# Sheet2.net
KiCad netlist of a schematic drawn in Altium Designer
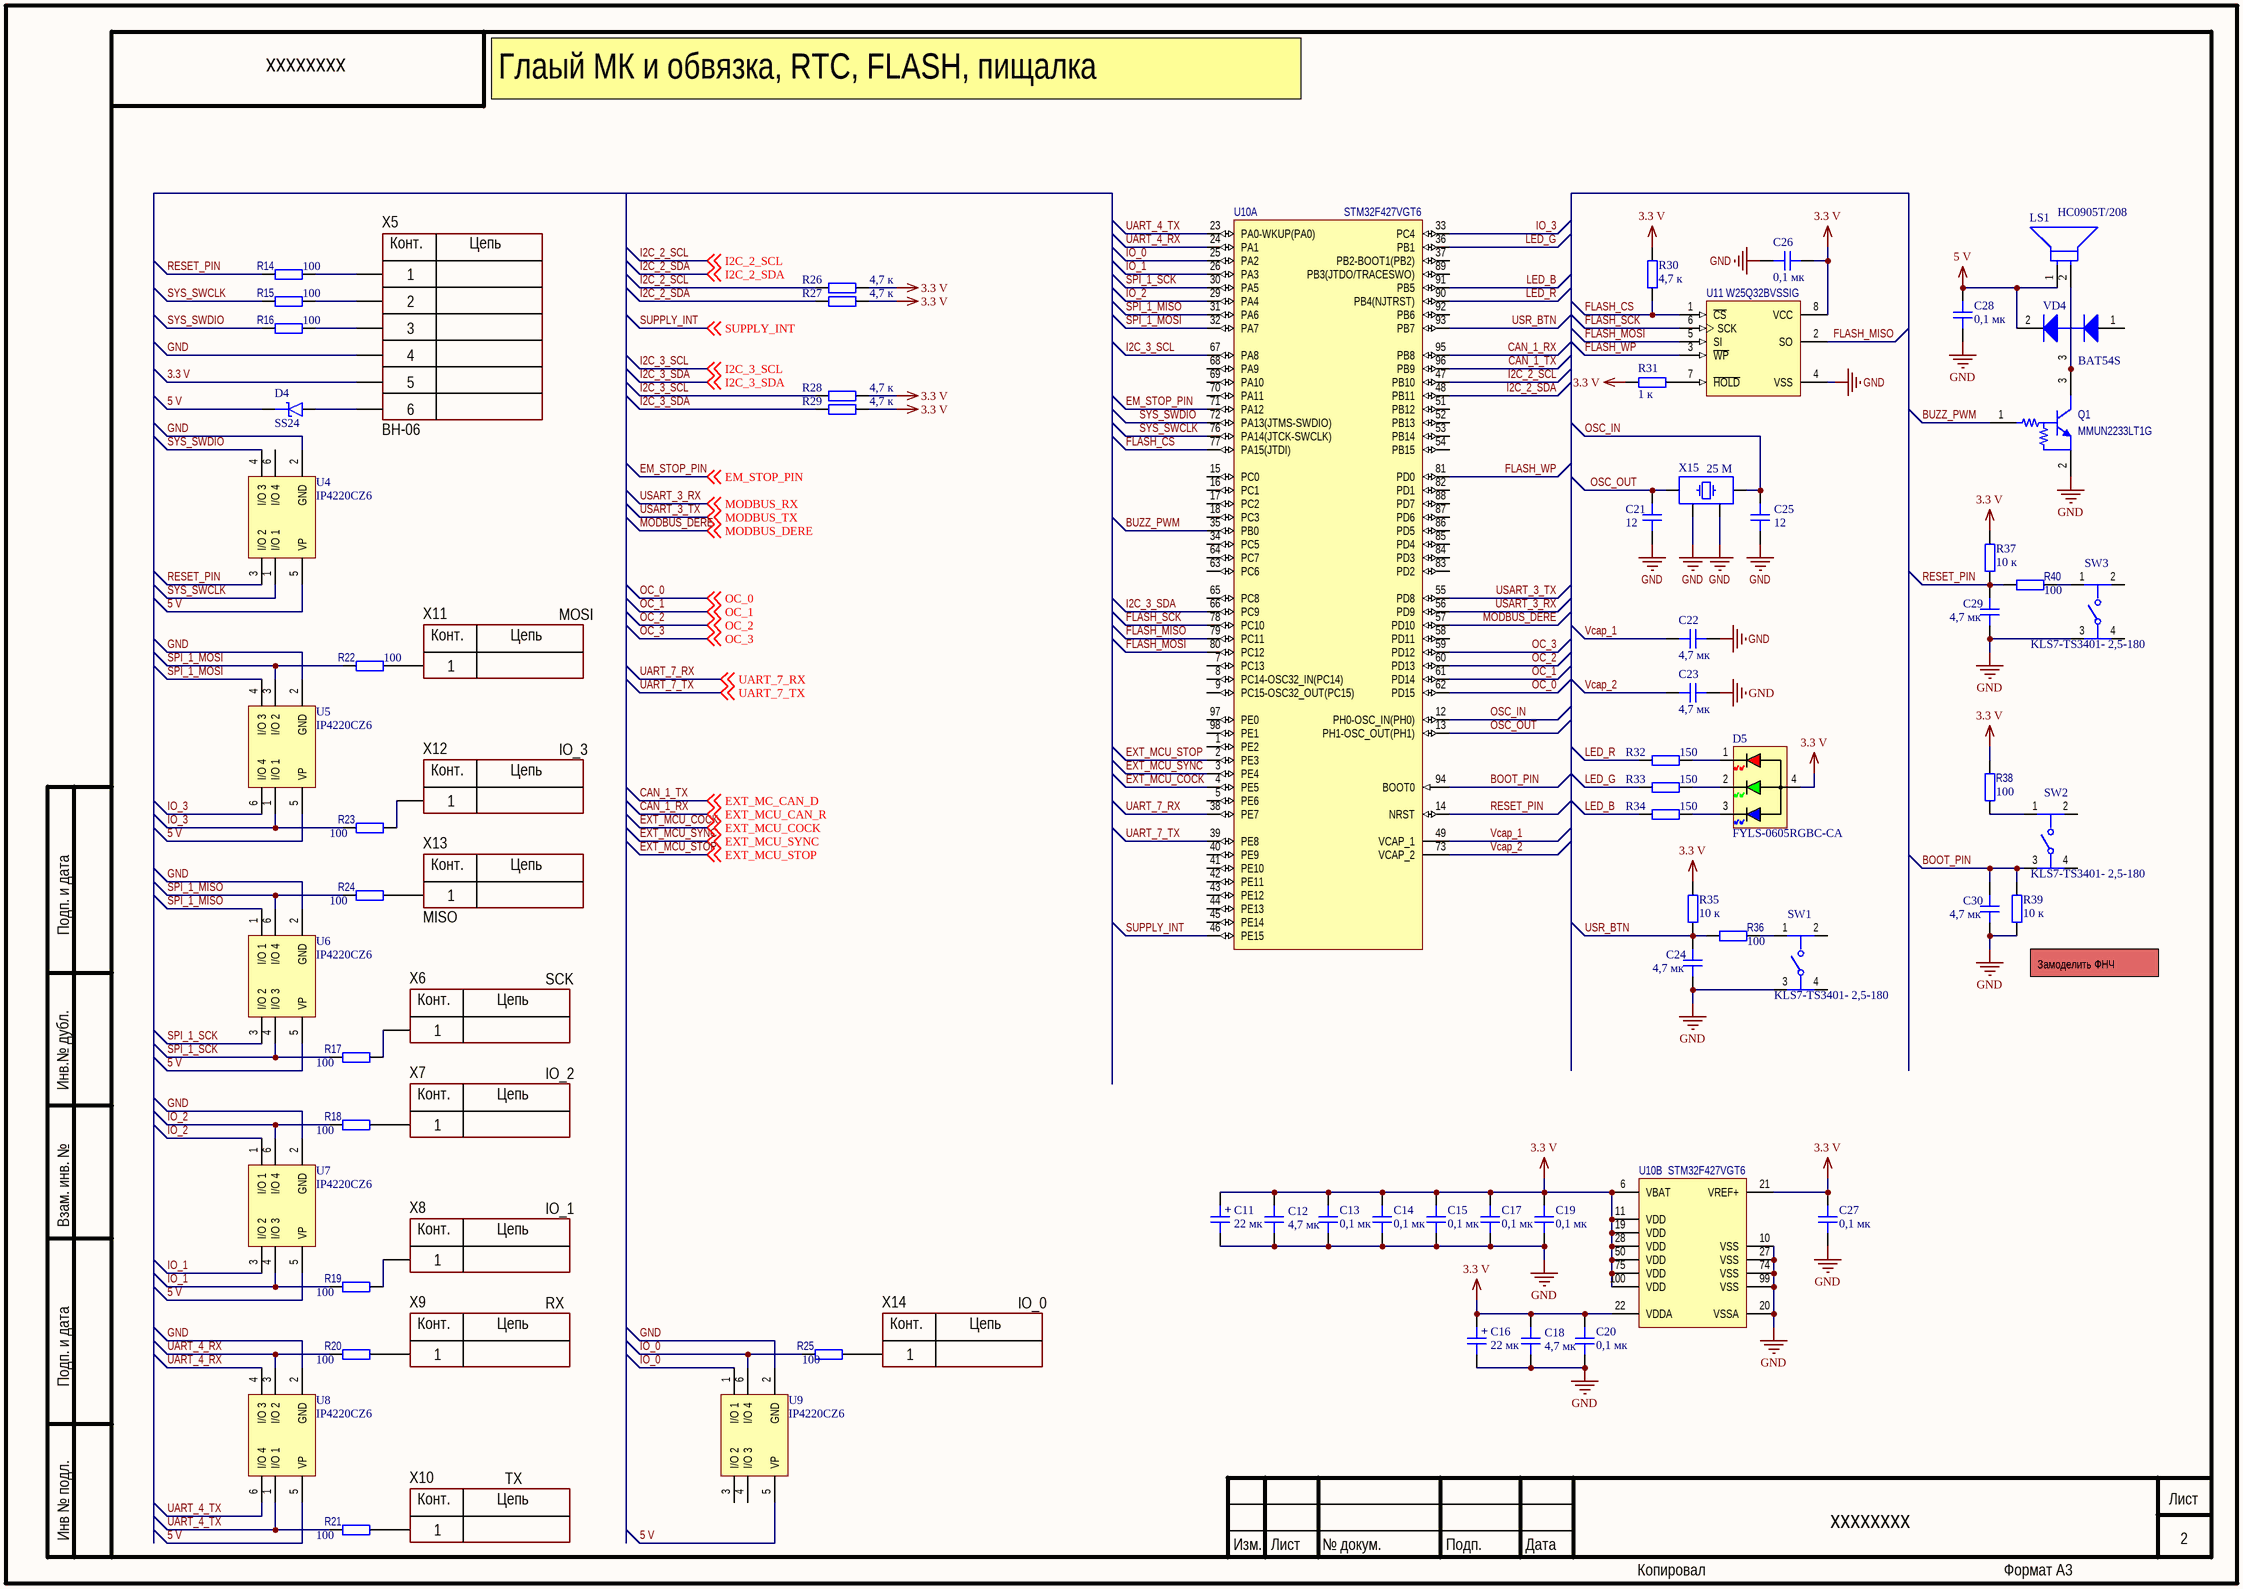
[diagram p0: Sheet2.SchDoc]

(export (version "E")
  (design (tool "Eeschema 10.0.6"))
  (components
    (comp (ref "C11")
      (value "22 мк")
      (footprint "TANTAL_B")
      (description "Танталовый конденсатор")
      (fields (field (name "VOLTAGE") "6,3"))
      (libsource (lib "Schematic-Lib-PhilsLab") (part "CAP_ALEL_16x16.5_25V"))
    )
    (comp (ref "C12")
      (value "4,7 мк")
      (footprint "CAP_0805")
      (description "Керамический конденсатор")
      (libsource (lib "Schematic-Lib-PhilsLab") (part "CAP_0805"))
    )
    (comp (ref "C13")
      (value "0,1 мк")
      (footprint "CAP_0603")
      (description "Керамический конденсатор")
      (libsource (lib "Schematic-Lib-PhilsLab") (part "CAP_0603"))
    )
    (comp (ref "C14")
      (value "0,1 мк")
      (footprint "CAP_0603")
      (description "Керамический конденсатор")
      (libsource (lib "Schematic-Lib-PhilsLab") (part "CAP_0603"))
    )
    (comp (ref "C15")
      (value "0,1 мк")
      (footprint "CAP_0603")
      (description "Керамический конденсатор")
      (libsource (lib "Schematic-Lib-PhilsLab") (part "CAP_0603"))
    )
    (comp (ref "C16")
      (value "22 мк")
      (footprint "TANTAL_B")
      (description "Танталовый конденсатор")
      (fields (field (name "VOLTAGE") "6,3"))
      (libsource (lib "Schematic-Lib-PhilsLab") (part "CAP_ALEL_16x16.5_25V"))
    )
    (comp (ref "C17")
      (value "0,1 мк")
      (footprint "CAP_0603")
      (description "Керамический конденсатор")
      (libsource (lib "Schematic-Lib-PhilsLab") (part "CAP_0603"))
    )
    (comp (ref "C18")
      (value "4,7 мк")
      (footprint "CAP_0805")
      (description "Керамический конденсатор")
      (libsource (lib "Schematic-Lib-PhilsLab") (part "CAP_0805"))
    )
    (comp (ref "C19")
      (value "0,1 мк")
      (footprint "CAP_0603")
      (description "Керамический конденсатор")
      (libsource (lib "Schematic-Lib-PhilsLab") (part "CAP_0603"))
    )
    (comp (ref "C20")
      (value "0,1 мк")
      (footprint "CAP_0603")
      (description "Керамический конденсатор")
      (libsource (lib "Schematic-Lib-PhilsLab") (part "CAP_0603"))
    )
    (comp (ref "C21")
      (value "12")
      (footprint "CAP_0603")
      (description "Керамический конденсатор")
      (libsource (lib "Schematic-Lib-PhilsLab") (part "CAP_0603"))
    )
    (comp (ref "C22")
      (value "4,7 мк")
      (footprint "CAP_0805")
      (description "Керамический конденсатор")
      (libsource (lib "Schematic-Lib-PhilsLab") (part "CAP_0805"))
    )
    (comp (ref "C23")
      (value "4,7 мк")
      (footprint "CAP_0805")
      (description "Керамический конденсатор")
      (libsource (lib "Schematic-Lib-PhilsLab") (part "CAP_0805"))
    )
    (comp (ref "C24")
      (value "4,7 мк")
      (footprint "CAP_0805")
      (description "Керамический конденсатор")
      (libsource (lib "Schematic-Lib-PhilsLab") (part "CAP_0805"))
    )
    (comp (ref "C25")
      (value "12")
      (footprint "CAP_0603")
      (description "Керамический конденсатор")
      (libsource (lib "Schematic-Lib-PhilsLab") (part "CAP_0603"))
    )
    (comp (ref "C26")
      (value "0,1 мк")
      (footprint "CAP_0603")
      (description "Керамический конденсатор")
      (libsource (lib "Schematic-Lib-PhilsLab") (part "CAP_0603"))
    )
    (comp (ref "C27")
      (value "0,1 мк")
      (footprint "CAP_0603")
      (description "Керамический конденсатор")
      (libsource (lib "Schematic-Lib-PhilsLab") (part "CAP_0603"))
    )
    (comp (ref "C28")
      (value "0,1 мк")
      (footprint "CAP_0603")
      (description "Керамический конденсатор")
      (libsource (lib "Schematic-Lib-PhilsLab") (part "CAP_0603"))
    )
    (comp (ref "C29")
      (value "4,7 мк")
      (footprint "CAP_0805")
      (description "Керамический конденсатор")
      (libsource (lib "Schematic-Lib-PhilsLab") (part "CAP_0805"))
    )
    (comp (ref "C30")
      (value "4,7 мк")
      (footprint "CAP_0805")
      (description "Керамический конденсатор")
      (libsource (lib "Schematic-Lib-PhilsLab") (part "CAP_0805"))
    )
    (comp (ref "D4")
      (value "SS24")
      (footprint "DO-214AC-2 (SMA)")
      (description "Диод")
      (libsource (lib "Schematic-Lib-PhilsLab") (part "D_SCHOTTKY_SMA"))
    )
    (comp (ref "D5")
      (value "FYLS-0605RGBC-CA")
      (footprint "150080M153000")
      (description "RGB светодиод")
      (libsource (lib "Schematic-Lib-PhilsLab") (part "150080M153000"))
    )
    (comp (ref "LS1")
      (value "HC0905T/208")
      (footprint "FP-SD1209-MFG")
      (description "Пищалка")
      (libsource (lib "Altium Content Vault") (part "1973c4b650225fd2ddacaff6b763965"))
    )
    (comp (ref "Q1")
      (value "MMUN2233LT1G")
      (footprint "ONSC-SOT-23-3-318-08_V")
      (description "npn транзистор с подтяжками")
      (libsource (lib "Altium Content Vault") (part "ONSC-BRT-NPN-B1E2C3-3"))
    )
    (comp (ref "R14")
      (value "100")
      (footprint "RES_0603")
      (description "Резистор")
      (libsource (lib "Schematic-Lib-PhilsLab") (part "RES_0603"))
    )
    (comp (ref "R15")
      (value "100")
      (footprint "RES_0603")
      (description "Резистор")
      (libsource (lib "Schematic-Lib-PhilsLab") (part "RES_0603"))
    )
    (comp (ref "R16")
      (value "100")
      (footprint "RES_0603")
      (description "Резистор")
      (libsource (lib "Schematic-Lib-PhilsLab") (part "RES_0603"))
    )
    (comp (ref "R17")
      (value "100")
      (footprint "RES_0603")
      (description "Резистор")
      (libsource (lib "Schematic-Lib-PhilsLab") (part "RES_0603"))
    )
    (comp (ref "R18")
      (value "100")
      (footprint "RES_0603")
      (description "Резистор")
      (libsource (lib "Schematic-Lib-PhilsLab") (part "RES_0603"))
    )
    (comp (ref "R19")
      (value "100")
      (footprint "RES_0603")
      (description "Резистор")
      (libsource (lib "Schematic-Lib-PhilsLab") (part "RES_0603"))
    )
    (comp (ref "R20")
      (value "100")
      (footprint "RES_0603")
      (description "Резистор")
      (libsource (lib "Schematic-Lib-PhilsLab") (part "RES_0603"))
    )
    (comp (ref "R21")
      (value "100")
      (footprint "RES_0603")
      (description "Резистор")
      (libsource (lib "Schematic-Lib-PhilsLab") (part "RES_0603"))
    )
    (comp (ref "R22")
      (value "100")
      (footprint "RES_0603")
      (description "Резистор")
      (libsource (lib "Schematic-Lib-PhilsLab") (part "RES_0603"))
    )
    (comp (ref "R23")
      (value "100")
      (footprint "RES_0603")
      (description "Резистор")
      (libsource (lib "Schematic-Lib-PhilsLab") (part "RES_0603"))
    )
    (comp (ref "R24")
      (value "100")
      (footprint "RES_0603")
      (description "Резистор")
      (libsource (lib "Schematic-Lib-PhilsLab") (part "RES_0603"))
    )
    (comp (ref "R25")
      (value "100")
      (footprint "RES_0603")
      (description "Резистор")
      (libsource (lib "Schematic-Lib-PhilsLab") (part "RES_0603"))
    )
    (comp (ref "R26")
      (value "4,7 к")
      (footprint "RES_0603")
      (description "Резистор")
      (libsource (lib "Schematic-Lib-PhilsLab") (part "RES_0603"))
    )
    (comp (ref "R27")
      (value "4,7 к")
      (footprint "RES_0603")
      (description "Резистор")
      (libsource (lib "Schematic-Lib-PhilsLab") (part "RES_0603"))
    )
    (comp (ref "R28")
      (value "4,7 к")
      (footprint "RES_0603")
      (description "Резистор")
      (libsource (lib "Schematic-Lib-PhilsLab") (part "RES_0603"))
    )
    (comp (ref "R29")
      (value "4,7 к")
      (footprint "RES_0603")
      (description "Резистор")
      (libsource (lib "Schematic-Lib-PhilsLab") (part "RES_0603"))
    )
    (comp (ref "R30")
      (value "4,7 к")
      (footprint "RES_0603")
      (description "Резистор")
      (libsource (lib "Schematic-Lib-PhilsLab") (part "RES_0603"))
    )
    (comp (ref "R31")
      (value "1 к")
      (footprint "RES_0603")
      (description "Резистор")
      (libsource (lib "Schematic-Lib-PhilsLab") (part "RES_0603"))
    )
    (comp (ref "R32")
      (value "150")
      (footprint "RES_0603")
      (description "Резистор")
      (libsource (lib "Schematic-Lib-PhilsLab") (part "RES_0603"))
    )
    (comp (ref "R33")
      (value "150")
      (footprint "RES_0603")
      (description "Резистор")
      (libsource (lib "Schematic-Lib-PhilsLab") (part "RES_0603"))
    )
    (comp (ref "R34")
      (value "150")
      (footprint "RES_0603")
      (description "Резистор")
      (libsource (lib "Schematic-Lib-PhilsLab") (part "RES_0603"))
    )
    (comp (ref "R35")
      (value "10 к")
      (footprint "RES_0603")
      (description "Резистор")
      (libsource (lib "Schematic-Lib-PhilsLab") (part "RES_0603"))
    )
    (comp (ref "R36")
      (value "100")
      (footprint "RES_0603")
      (description "Резистор")
      (libsource (lib "Schematic-Lib-PhilsLab") (part "RES_0603"))
    )
    (comp (ref "R37")
      (value "10 к")
      (footprint "RES_0603")
      (description "Резистор")
      (libsource (lib "Schematic-Lib-PhilsLab") (part "RES_0603"))
    )
    (comp (ref "R38")
      (value "100")
      (footprint "RES_0603")
      (description "Резистор")
      (libsource (lib "Schematic-Lib-PhilsLab") (part "RES_0603"))
    )
    (comp (ref "R39")
      (value "10 к")
      (footprint "RES_0603")
      (description "Резистор")
      (libsource (lib "Schematic-Lib-PhilsLab") (part "RES_0603"))
    )
    (comp (ref "R40")
      (value "100")
      (footprint "RES_0603")
      (description "Резистор")
      (libsource (lib "Schematic-Lib-PhilsLab") (part "RES_0603"))
    )
    (comp (ref "SW1")
      (value "KLS7-TS3401- 2,5-180")
      (footprint "FP-PTS810_SJG_250_SMTR_LF-MFG")
      (description "Кнопка")
      (libsource (lib "Altium Content Vault") (part "1adf0dd01260c80cf25a44bfd6b99ba"))
    )
    (comp (ref "SW2")
      (value "KLS7-TS3401- 2,5-180")
      (footprint "FP-PTS810_SJG_250_SMTR_LF-MFG")
      (description "Кнопка")
      (libsource (lib "Altium Content Vault") (part "1adf0dd01260c80cf25a44bfd6b99ba"))
    )
    (comp (ref "SW3")
      (value "KLS7-TS3401- 2,5-180")
      (footprint "FP-PTS810_SJG_250_SMTR_LF-MFG")
      (description "Кнопка")
      (libsource (lib "Altium Content Vault") (part "1adf0dd01260c80cf25a44bfd6b99ba"))
    )
    (comp (ref "U4")
      (value "IP4220CZ6")
      (footprint "NXP-SOT457_L")
      (description "Сборка защитных диодов")
      (libsource (lib "") (part "NXP-IP4220CZ6-6_2"))
    )
    (comp (ref "U5")
      (value "IP4220CZ6")
      (footprint "NXP-SOT457_L")
      (description "Сборка защитных диодов")
      (libsource (lib "") (part "NXP-IP4220CZ6-6_1"))
    )
    (comp (ref "U6")
      (value "IP4220CZ6")
      (footprint "NXP-SOT457_L")
      (description "Сборка защитных диодов")
      (libsource (lib "Altium Content Vault") (part "NXP-IP4220CZ6-6"))
    )
    (comp (ref "U7")
      (value "IP4220CZ6")
      (footprint "NXP-SOT457_L")
      (description "Сборка защитных диодов")
      (libsource (lib "Altium Content Vault") (part "NXP-IP4220CZ6-6"))
    )
    (comp (ref "U8")
      (value "IP4220CZ6")
      (footprint "NXP-SOT457_L")
      (description "Сборка защитных диодов")
      (libsource (lib "") (part "NXP-IP4220CZ6-6_1"))
    )
    (comp (ref "U9")
      (value "IP4220CZ6")
      (footprint "NXP-SOT457_L")
      (description "Сборка защитных диодов")
      (libsource (lib "Altium Content Vault") (part "NXP-IP4220CZ6-6"))
    )
    (comp (ref "U10")
      (value "STM32F427VGT6")
      (footprint "STM-LQFP100_M")
      (description "Микроконтроллер")
      (libsource (lib "") (part "MC-ARM-STM32F4X7-SQ100_1"))
    )
    (comp (ref "U11")
      (value "W25Q32BVSSIG")
      (footprint "SOIJ-SM8_L")
      (description "FLASH память")
      (libsource (lib "Altium Content Vault") (part "MEM-SEEPROM-25AA1024-8"))
    )
    (comp (ref "VD4")
      (value "BAT54S")
      (footprint "ONSC-SOT-323-3-419-04_V")
      (description "Пара последовательных диодов")
      (libsource (lib "Altium Content Vault") (part "ONSC-D-A1K2C3-3"))
    )
    (comp (ref "X5")
      (value "BH-06")
      (footprint "CON: IDC-6MS")
      (description "Коннектор под IDC-6")
      (libsource (lib "Connectors") (part "6-Connector"))
    )
    (comp (ref "X6")
      (value "SCK")
      (footprint "CON: PADS 1x1mm")
      (libsource (lib "Connectors") (part "1-Connector"))
    )
    (comp (ref "X7")
      (value "IO_2")
      (footprint "CON: PADS 1x1mm")
      (libsource (lib "Connectors") (part "1-Connector"))
    )
    (comp (ref "X8")
      (value "IO_1")
      (footprint "CON: PADS 1x1mm")
      (libsource (lib "Connectors") (part "1-Connector"))
    )
    (comp (ref "X9")
      (value "RX")
      (footprint "CON: PADS 1x1mm")
      (libsource (lib "Connectors") (part "1-Connector"))
    )
    (comp (ref "X10")
      (value "TX")
      (footprint "CON: PADS 1x1mm")
      (libsource (lib "Connectors") (part "1-Connector"))
    )
    (comp (ref "X11")
      (value "MOSI")
      (footprint "CON: PADS 1x1mm")
      (libsource (lib "Connectors") (part "1-Connector"))
    )
    (comp (ref "X12")
      (value "IO_3")
      (footprint "CON: PADS 1x1mm")
      (libsource (lib "Connectors") (part "1-Connector"))
    )
    (comp (ref "X13")
      (value "MISO")
      (footprint "CON: PADS 1x1mm")
      (libsource (lib "Connectors") (part "1-Connector"))
    )
    (comp (ref "X14")
      (value "IO_0")
      (footprint "CON: PADS 1x1mm")
      (libsource (lib "Connectors") (part "1-Connector"))
    )
    (comp (ref "X15")
      (value "25 M")
      (footprint "XTAL_3225")
      (description "Кварцевый резонатор")
      (libsource (lib "Schematic-Lib-PhilsLab") (part "TSX-3225_24.0000MF15X-AC"))
    )
  )
  (nets
    (net (code "1") (name "/BOOT_PIN") (class "Default")
      (node (ref "C30") (pin "1") (pinfunction "1_1") (pintype "passive"))
      (node (ref "R39") (pin "1") (pinfunction "1_1") (pintype "passive"))
      (node (ref "SW2") (pin "3") (pinfunction "3_3") (pintype "passive"))
      (node (ref "U10") (pin "94") (pinfunction "BOOT0_94") (pintype "input"))
    )
    (net (code "2") (name "/BUZZ_PWM") (class "Default")
      (node (ref "Q1") (pin "1") (pinfunction "B_1") (pintype "passive"))
      (node (ref "U10") (pin "35") (pinfunction "PB0_35") (pintype "bidirectional"))
    )
    (net (code "3") (name "/FLASH_CS") (class "Default")
      (node (ref "R30") (pin "1") (pinfunction "1_1") (pintype "passive"))
      (node (ref "U10") (pin "77") (pinfunction "PA15(JTDI)_77") (pintype "bidirectional"))
      (node (ref "U11") (pin "1") (pinfunction "~{CS}_1") (pintype "input"))
    )
    (net (code "4") (name "/FLASH_MISO") (class "Default")
      (node (ref "U10") (pin "79") (pinfunction "PC11_79") (pintype "bidirectional"))
      (node (ref "U11") (pin "2") (pinfunction "SO_2") (pintype "tri_state"))
    )
    (net (code "5") (name "/FLASH_MOSI") (class "Default")
      (node (ref "U10") (pin "80") (pinfunction "PC12_80") (pintype "bidirectional"))
      (node (ref "U11") (pin "5") (pinfunction "SI_5") (pintype "input"))
    )
    (net (code "6") (name "/FLASH_SCK") (class "Default")
      (node (ref "U10") (pin "78") (pinfunction "PC10_78") (pintype "bidirectional"))
      (node (ref "U11") (pin "6") (pinfunction "SCK_6") (pintype "input"))
    )
    (net (code "7") (name "/FLASH_WP") (class "Default")
      (node (ref "U10") (pin "81") (pinfunction "PD0_81") (pintype "bidirectional"))
      (node (ref "U11") (pin "3") (pinfunction "~{WP}_3") (pintype "input"))
    )
    (net (code "8") (name "/IO_0") (class "Default")
      (node (ref "R25") (pin "1") (pinfunction "1_1") (pintype "passive"))
      (node (ref "U10") (pin "25") (pinfunction "PA2_25") (pintype "bidirectional"))
      (node (ref "U9") (pin "1") (pinfunction "I/O_1_1") (pintype "passive"))
      (node (ref "U9") (pin "6") (pinfunction "I/O_4_6") (pintype "passive"))
    )
    (net (code "9") (name "/IO_1") (class "Default")
      (node (ref "R19") (pin "1") (pinfunction "1_1") (pintype "passive"))
      (node (ref "U10") (pin "26") (pinfunction "PA3_26") (pintype "bidirectional"))
      (node (ref "U7") (pin "3") (pinfunction "I/O_2_3") (pintype "passive"))
      (node (ref "U7") (pin "4") (pinfunction "I/O_3_4") (pintype "passive"))
    )
    (net (code "10") (name "/IO_2") (class "Default")
      (node (ref "R18") (pin "1") (pinfunction "1_1") (pintype "passive"))
      (node (ref "U10") (pin "29") (pinfunction "PA4_29") (pintype "bidirectional"))
      (node (ref "U7") (pin "1") (pinfunction "I/O_1_1") (pintype "passive"))
      (node (ref "U7") (pin "6") (pinfunction "I/O_4_6") (pintype "passive"))
    )
    (net (code "11") (name "/IO_3") (class "Default")
      (node (ref "R23") (pin "1") (pinfunction "1_1") (pintype "passive"))
      (node (ref "U10") (pin "33") (pinfunction "PC4_33") (pintype "bidirectional"))
      (node (ref "U5") (pin "1") (pinfunction "I/O_1_1") (pintype "passive"))
      (node (ref "U5") (pin "6") (pinfunction "I/O_4_6") (pintype "passive"))
    )
    (net (code "12") (name "/LED_B") (class "Default")
      (node (ref "R34") (pin "1") (pinfunction "1_1") (pintype "passive"))
      (node (ref "U10") (pin "91") (pinfunction "PB5_91") (pintype "bidirectional"))
    )
    (net (code "13") (name "/LED_G") (class "Default")
      (node (ref "R33") (pin "1") (pinfunction "1_1") (pintype "passive"))
      (node (ref "U10") (pin "36") (pinfunction "PB1_36") (pintype "bidirectional"))
    )
    (net (code "14") (name "/LED_R") (class "Default")
      (node (ref "R32") (pin "1") (pinfunction "1_1") (pintype "passive"))
      (node (ref "U10") (pin "90") (pinfunction "PB4(NJTRST)_90") (pintype "bidirectional"))
    )
    (net (code "15") (name "/OSC_IN") (class "Default")
      (node (ref "C25") (pin "1") (pinfunction "1_1") (pintype "passive"))
      (node (ref "U10") (pin "12") (pinfunction "PH0-OSC_IN(PH0)_12") (pintype "bidirectional"))
      (node (ref "X15") (pin "3") (pinfunction "3_3") (pintype "passive"))
    )
    (net (code "16") (name "/OSC_OUT") (class "Default")
      (node (ref "C21") (pin "1") (pinfunction "1_1") (pintype "passive"))
      (node (ref "U10") (pin "13") (pinfunction "PH1-OSC_OUT(PH1)_13") (pintype "bidirectional"))
      (node (ref "X15") (pin "1") (pinfunction "1_1") (pintype "passive"))
    )
    (net (code "17") (name "/RESET_PIN") (class "Default")
      (node (ref "C29") (pin "1") (pinfunction "1_1") (pintype "passive"))
      (node (ref "R14") (pin "1") (pinfunction "1_1") (pintype "passive"))
      (node (ref "R37") (pin "2") (pinfunction "2_2") (pintype "passive"))
      (node (ref "R40") (pin "2") (pinfunction "2_2") (pintype "passive"))
      (node (ref "U10") (pin "14") (pinfunction "NRST_14") (pintype "bidirectional"))
      (node (ref "U4") (pin "3") (pinfunction "I/O_2_3") (pintype "passive"))
    )
    (net (code "18") (name "/SPI_1_MISO") (class "Default")
      (node (ref "R24") (pin "1") (pinfunction "1_1") (pintype "passive"))
      (node (ref "U10") (pin "31") (pinfunction "PA6_31") (pintype "bidirectional"))
      (node (ref "U6") (pin "1") (pinfunction "I/O_1_1") (pintype "passive"))
      (node (ref "U6") (pin "6") (pinfunction "I/O_4_6") (pintype "passive"))
    )
    (net (code "19") (name "/SPI_1_MOSI") (class "Default")
      (node (ref "R22") (pin "1") (pinfunction "1_1") (pintype "passive"))
      (node (ref "U10") (pin "32") (pinfunction "PA7_32") (pintype "bidirectional"))
      (node (ref "U5") (pin "3") (pinfunction "I/O_2_3") (pintype "passive"))
      (node (ref "U5") (pin "4") (pinfunction "I/O_3_4") (pintype "passive"))
    )
    (net (code "20") (name "/SPI_1_SCK") (class "Default")
      (node (ref "R17") (pin "1") (pinfunction "1_1") (pintype "passive"))
      (node (ref "U10") (pin "30") (pinfunction "PA5_30") (pintype "bidirectional"))
      (node (ref "U6") (pin "3") (pinfunction "I/O_2_3") (pintype "passive"))
      (node (ref "U6") (pin "4") (pinfunction "I/O_3_4") (pintype "passive"))
    )
    (net (code "21") (name "/SYS_SWCLK") (class "Default")
      (node (ref "R15") (pin "1") (pinfunction "1_1") (pintype "passive"))
      (node (ref "U10") (pin "76") (pinfunction "PA14(JTCK-SWCLK)_76") (pintype "bidirectional"))
      (node (ref "U4") (pin "1") (pinfunction "I/O_1_1") (pintype "passive"))
    )
    (net (code "22") (name "/SYS_SWDIO") (class "Default")
      (node (ref "R16") (pin "1") (pinfunction "1_1") (pintype "passive"))
      (node (ref "U10") (pin "72") (pinfunction "PA13(JTMS-SWDIO)_72") (pintype "bidirectional"))
      (node (ref "U4") (pin "4") (pinfunction "I/O_3_4") (pintype "passive"))
    )
    (net (code "23") (name "/UART_4_RX") (class "Default")
      (node (ref "R20") (pin "1") (pinfunction "1_1") (pintype "passive"))
      (node (ref "U10") (pin "24") (pinfunction "PA1_24") (pintype "bidirectional"))
      (node (ref "U8") (pin "3") (pinfunction "I/O_2_3") (pintype "passive"))
      (node (ref "U8") (pin "4") (pinfunction "I/O_3_4") (pintype "passive"))
    )
    (net (code "24") (name "/UART_4_TX") (class "Default")
      (node (ref "R21") (pin "1") (pinfunction "1_1") (pintype "passive"))
      (node (ref "U10") (pin "23") (pinfunction "PA0-WKUP(PA0)_23") (pintype "bidirectional"))
      (node (ref "U8") (pin "1") (pinfunction "I/O_1_1") (pintype "passive"))
      (node (ref "U8") (pin "6") (pinfunction "I/O_4_6") (pintype "passive"))
    )
    (net (code "25") (name "/USR_BTN") (class "Default")
      (node (ref "C24") (pin "1") (pinfunction "1_1") (pintype "passive"))
      (node (ref "R35") (pin "2") (pinfunction "2_2") (pintype "passive"))
      (node (ref "R36") (pin "2") (pinfunction "2_2") (pintype "passive"))
      (node (ref "U10") (pin "93") (pinfunction "PB7_93") (pintype "bidirectional"))
    )
    (net (code "26") (name "/Vcap_1") (class "Default")
      (node (ref "C22") (pin "2") (pinfunction "2_2") (pintype "passive"))
      (node (ref "U10") (pin "49") (pinfunction "VCAP_1_49") (pintype "power_in"))
    )
    (net (code "27") (name "/Vcap_2") (class "Default")
      (node (ref "C23") (pin "2") (pinfunction "2_2") (pintype "passive"))
      (node (ref "U10") (pin "73") (pinfunction "VCAP_2_73") (pintype "power_in"))
    )
    (net (code "28") (name "3.3 V") (class "Default")
      (node (ref "C11") (pin "1") (pinfunction "1_1") (pintype "passive"))
      (node (ref "C12") (pin "1") (pinfunction "1_1") (pintype "passive"))
      (node (ref "C13") (pin "1") (pinfunction "1_1") (pintype "passive"))
      (node (ref "C14") (pin "1") (pinfunction "1_1") (pintype "passive"))
      (node (ref "C15") (pin "1") (pinfunction "1_1") (pintype "passive"))
      (node (ref "C16") (pin "1") (pinfunction "1_1") (pintype "passive"))
      (node (ref "C17") (pin "1") (pinfunction "1_1") (pintype "passive"))
      (node (ref "C18") (pin "1") (pinfunction "1_1") (pintype "passive"))
      (node (ref "C19") (pin "1") (pinfunction "1_1") (pintype "passive"))
      (node (ref "C20") (pin "1") (pinfunction "1_1") (pintype "passive"))
      (node (ref "C26") (pin "2") (pinfunction "2_2") (pintype "passive"))
      (node (ref "C27") (pin "1") (pinfunction "1_1") (pintype "passive"))
      (node (ref "D5") (pin "4") (pinfunction "AC_4") (pintype "passive"))
      (node (ref "R26") (pin "2") (pinfunction "2_2") (pintype "passive"))
      (node (ref "R27") (pin "2") (pinfunction "2_2") (pintype "passive"))
      (node (ref "R28") (pin "2") (pinfunction "2_2") (pintype "passive"))
      (node (ref "R29") (pin "2") (pinfunction "2_2") (pintype "passive"))
      (node (ref "R30") (pin "2") (pinfunction "2_2") (pintype "passive"))
      (node (ref "R31") (pin "1") (pinfunction "1_1") (pintype "passive"))
      (node (ref "R35") (pin "1") (pinfunction "1_1") (pintype "passive"))
      (node (ref "R37") (pin "1") (pinfunction "1_1") (pintype "passive"))
      (node (ref "R38") (pin "2") (pinfunction "2_2") (pintype "passive"))
      (node (ref "U10") (pin "100") (pinfunction "VDD_100") (pintype "power_in"))
      (node (ref "U10") (pin "11") (pinfunction "VDD_11") (pintype "power_in"))
      (node (ref "U10") (pin "19") (pinfunction "VDD_19") (pintype "power_in"))
      (node (ref "U10") (pin "21") (pinfunction "VREF+_21") (pintype "power_in"))
      (node (ref "U10") (pin "22") (pinfunction "VDDA_22") (pintype "power_in"))
      (node (ref "U10") (pin "28") (pinfunction "VDD_28") (pintype "power_in"))
      (node (ref "U10") (pin "50") (pinfunction "VDD_50") (pintype "power_in"))
      (node (ref "U10") (pin "6") (pinfunction "VBAT_6") (pintype "power_in"))
      (node (ref "U10") (pin "75") (pinfunction "VDD_75") (pintype "power_in"))
      (node (ref "U11") (pin "8") (pinfunction "VCC_8") (pintype "power_in"))
      (node (ref "X5") (pin "5") (pinfunction "5_5") (pintype "power_in"))
    )
    (net (code "29") (name "5 V") (class "Default")
      (node (ref "C28") (pin "1") (pinfunction "1_1") (pintype "passive"))
      (node (ref "D4") (pin "K") (pinfunction "K_K") (pintype "passive"))
      (node (ref "LS1") (pin "1") (pinfunction "C_1") (pintype "passive"))
      (node (ref "U4") (pin "5") (pinfunction "VP_5") (pintype "power_in"))
      (node (ref "U5") (pin "5") (pinfunction "VP_5") (pintype "power_in"))
      (node (ref "U6") (pin "5") (pinfunction "VP_5") (pintype "power_in"))
      (node (ref "U7") (pin "5") (pinfunction "VP_5") (pintype "power_in"))
      (node (ref "U8") (pin "5") (pinfunction "VP_5") (pintype "power_in"))
      (node (ref "U9") (pin "5") (pinfunction "VP_5") (pintype "power_in"))
      (node (ref "VD4") (pin "2") (pinfunction "K_2") (pintype "passive"))
    )
    (net (code "30") (name "EM_STOP_PIN") (class "Default")
      (node (ref "U10") (pin "71") (pinfunction "PA12_71") (pintype "bidirectional"))
    )
    (net (code "31") (name "EXT_MCU_CAN_R") (class "Default")
      (node (ref "U10") (pin "95") (pinfunction "PB8_95") (pintype "bidirectional"))
    )
    (net (code "32") (name "EXT_MCU_COCK") (class "Default")
      (node (ref "U10") (pin "4") (pinfunction "PE5_4") (pintype "bidirectional"))
    )
    (net (code "33") (name "EXT_MCU_STOP") (class "Default")
      (node (ref "U10") (pin "2") (pinfunction "PE3_2") (pintype "bidirectional"))
    )
    (net (code "34") (name "EXT_MCU_SYNC") (class "Default")
      (node (ref "U10") (pin "3") (pinfunction "PE4_3") (pintype "bidirectional"))
    )
    (net (code "35") (name "EXT_MC_CAN_D") (class "Default")
      (node (ref "U10") (pin "96") (pinfunction "PB9_96") (pintype "bidirectional"))
    )
    (net (code "36") (name "GND") (class "Default")
      (node (ref "C11") (pin "2") (pinfunction "2_2") (pintype "passive"))
      (node (ref "C12") (pin "2") (pinfunction "2_2") (pintype "passive"))
      (node (ref "C13") (pin "2") (pinfunction "2_2") (pintype "passive"))
      (node (ref "C14") (pin "2") (pinfunction "2_2") (pintype "passive"))
      (node (ref "C15") (pin "2") (pinfunction "2_2") (pintype "passive"))
      (node (ref "C16") (pin "2") (pinfunction "2_2") (pintype "passive"))
      (node (ref "C17") (pin "2") (pinfunction "2_2") (pintype "passive"))
      (node (ref "C18") (pin "2") (pinfunction "2_2") (pintype "passive"))
      (node (ref "C19") (pin "2") (pinfunction "2_2") (pintype "passive"))
      (node (ref "C20") (pin "2") (pinfunction "2_2") (pintype "passive"))
      (node (ref "C21") (pin "2") (pinfunction "2_2") (pintype "passive"))
      (node (ref "C22") (pin "1") (pinfunction "1_1") (pintype "passive"))
      (node (ref "C23") (pin "1") (pinfunction "1_1") (pintype "passive"))
      (node (ref "C24") (pin "2") (pinfunction "2_2") (pintype "passive"))
      (node (ref "C25") (pin "2") (pinfunction "2_2") (pintype "passive"))
      (node (ref "C26") (pin "1") (pinfunction "1_1") (pintype "passive"))
      (node (ref "C27") (pin "2") (pinfunction "2_2") (pintype "passive"))
      (node (ref "C28") (pin "2") (pinfunction "2_2") (pintype "passive"))
      (node (ref "C29") (pin "2") (pinfunction "2_2") (pintype "passive"))
      (node (ref "C30") (pin "2") (pinfunction "2_2") (pintype "passive"))
      (node (ref "Q1") (pin "2") (pinfunction "E_2") (pintype "passive"))
      (node (ref "R39") (pin "2") (pinfunction "2_2") (pintype "passive"))
      (node (ref "SW1") (pin "3") (pinfunction "3_3") (pintype "passive"))
      (node (ref "SW3") (pin "3") (pinfunction "3_3") (pintype "passive"))
      (node (ref "U10") (pin "10") (pinfunction "VSS_10") (pintype "power_in"))
      (node (ref "U10") (pin "20") (pinfunction "VSSA_20") (pintype "power_in"))
      (node (ref "U10") (pin "27") (pinfunction "VSS_27") (pintype "power_in"))
      (node (ref "U10") (pin "74") (pinfunction "VSS_74") (pintype "power_in"))
      (node (ref "U10") (pin "99") (pinfunction "VSS_99") (pintype "power_in"))
      (node (ref "U11") (pin "4") (pinfunction "VSS_4") (pintype "power_in"))
      (node (ref "U4") (pin "2") (pinfunction "GND_2") (pintype "power_in"))
      (node (ref "U5") (pin "2") (pinfunction "GND_2") (pintype "power_in"))
      (node (ref "U6") (pin "2") (pinfunction "GND_2") (pintype "power_in"))
      (node (ref "U7") (pin "2") (pinfunction "GND_2") (pintype "power_in"))
      (node (ref "U8") (pin "2") (pinfunction "GND_2") (pintype "power_in"))
      (node (ref "U9") (pin "2") (pinfunction "GND_2") (pintype "power_in"))
      (node (ref "X15") (pin "2") (pinfunction "2_2") (pintype "passive"))
      (node (ref "X15") (pin "4") (pinfunction "4_4") (pintype "passive"))
      (node (ref "X5") (pin "4") (pinfunction "4_4") (pintype "power_in"))
    )
    (net (code "37") (name "I2C_2_SCL") (class "Default")
      (node (ref "R26") (pin "1") (pinfunction "1_1") (pintype "passive"))
      (node (ref "U10") (pin "47") (pinfunction "PB10_47") (pintype "bidirectional"))
    )
    (net (code "38") (name "I2C_2_SDA") (class "Default")
      (node (ref "R27") (pin "1") (pinfunction "1_1") (pintype "passive"))
      (node (ref "U10") (pin "48") (pinfunction "PB11_48") (pintype "bidirectional"))
    )
    (net (code "39") (name "I2C_3_SCL") (class "Default")
      (node (ref "R28") (pin "1") (pinfunction "1_1") (pintype "passive"))
      (node (ref "U10") (pin "67") (pinfunction "PA8_67") (pintype "bidirectional"))
    )
    (net (code "40") (name "I2C_3_SDA") (class "Default")
      (node (ref "R29") (pin "1") (pinfunction "1_1") (pintype "passive"))
      (node (ref "U10") (pin "66") (pinfunction "PC9_66") (pintype "bidirectional"))
    )
    (net (code "41") (name "MODBUS_DERE") (class "Default")
      (node (ref "U10") (pin "57") (pinfunction "PD10_57") (pintype "bidirectional"))
    )
    (net (code "42") (name "MODBUS_RX") (class "Default")
      (node (ref "U10") (pin "56") (pinfunction "PD9_56") (pintype "bidirectional"))
    )
    (net (code "43") (name "MODBUS_TX") (class "Default")
      (node (ref "U10") (pin "55") (pinfunction "PD8_55") (pintype "bidirectional"))
    )
    (net (code "44") (name "Net-(D4-PadA)") (class "Default")
      (node (ref "D4") (pin "A") (pinfunction "A_A") (pintype "passive"))
      (node (ref "X5") (pin "6") (pinfunction "6_6") (pintype "power_in"))
    )
    (net (code "45") (name "Net-(D5-CB)") (class "Default")
      (node (ref "D5") (pin "3") (pinfunction "CB_3") (pintype "passive"))
      (node (ref "R34") (pin "2") (pinfunction "2_2") (pintype "passive"))
    )
    (net (code "46") (name "Net-(D5-CG)") (class "Default")
      (node (ref "D5") (pin "2") (pinfunction "CG_2") (pintype "passive"))
      (node (ref "R33") (pin "2") (pinfunction "2_2") (pintype "passive"))
    )
    (net (code "47") (name "Net-(D5-CR)") (class "Default")
      (node (ref "D5") (pin "1") (pinfunction "CR_1") (pintype "passive"))
      (node (ref "R32") (pin "2") (pinfunction "2_2") (pintype "passive"))
    )
    (net (code "48") (name "Net-(LS1-A)") (class "Default")
      (node (ref "LS1") (pin "2") (pinfunction "A_2") (pintype "passive"))
      (node (ref "Q1") (pin "3") (pinfunction "C_3") (pintype "passive"))
      (node (ref "VD4") (pin "3") (pinfunction "K/A_3") (pintype "passive"))
    )
    (net (code "49") (name "Net-(R14-Pad2)") (class "Default")
      (node (ref "R14") (pin "2") (pinfunction "2_2") (pintype "passive"))
      (node (ref "X5") (pin "1") (pinfunction "1_1") (pintype "passive"))
    )
    (net (code "50") (name "Net-(R15-Pad2)") (class "Default")
      (node (ref "R15") (pin "2") (pinfunction "2_2") (pintype "passive"))
      (node (ref "X5") (pin "2") (pinfunction "2_2") (pintype "passive"))
    )
    (net (code "51") (name "Net-(R16-Pad2)") (class "Default")
      (node (ref "R16") (pin "2") (pinfunction "2_2") (pintype "passive"))
      (node (ref "X5") (pin "3") (pinfunction "3_3") (pintype "power_in"))
    )
    (net (code "52") (name "Net-(R17-Pad2)") (class "Default")
      (node (ref "R17") (pin "2") (pinfunction "2_2") (pintype "passive"))
      (node (ref "X6") (pin "1") (pinfunction "1_1") (pintype "passive"))
    )
    (net (code "53") (name "Net-(R18-Pad2)") (class "Default")
      (node (ref "R18") (pin "2") (pinfunction "2_2") (pintype "passive"))
      (node (ref "X7") (pin "1") (pinfunction "1_1") (pintype "passive"))
    )
    (net (code "54") (name "Net-(R19-Pad2)") (class "Default")
      (node (ref "R19") (pin "2") (pinfunction "2_2") (pintype "passive"))
      (node (ref "X8") (pin "1") (pinfunction "1_1") (pintype "passive"))
    )
    (net (code "55") (name "Net-(R20-Pad2)") (class "Default")
      (node (ref "R20") (pin "2") (pinfunction "2_2") (pintype "passive"))
      (node (ref "X9") (pin "1") (pinfunction "1_1") (pintype "passive"))
    )
    (net (code "56") (name "Net-(R21-Pad2)") (class "Default")
      (node (ref "R21") (pin "2") (pinfunction "2_2") (pintype "passive"))
      (node (ref "X10") (pin "1") (pinfunction "1_1") (pintype "passive"))
    )
    (net (code "57") (name "Net-(R22-Pad2)") (class "Default")
      (node (ref "R22") (pin "2") (pinfunction "2_2") (pintype "passive"))
      (node (ref "X11") (pin "1") (pinfunction "1_1") (pintype "passive"))
    )
    (net (code "58") (name "Net-(R23-Pad2)") (class "Default")
      (node (ref "R23") (pin "2") (pinfunction "2_2") (pintype "passive"))
      (node (ref "X12") (pin "1") (pinfunction "1_1") (pintype "passive"))
    )
    (net (code "59") (name "Net-(R24-Pad2)") (class "Default")
      (node (ref "R24") (pin "2") (pinfunction "2_2") (pintype "passive"))
      (node (ref "X13") (pin "1") (pinfunction "1_1") (pintype "passive"))
    )
    (net (code "60") (name "Net-(R25-Pad2)") (class "Default")
      (node (ref "R25") (pin "2") (pinfunction "2_2") (pintype "passive"))
      (node (ref "X14") (pin "1") (pinfunction "1_1") (pintype "passive"))
    )
    (net (code "61") (name "Net-(R36-Pad1)") (class "Default")
      (node (ref "R36") (pin "1") (pinfunction "1_1") (pintype "passive"))
      (node (ref "SW1") (pin "1") (pinfunction "1_1") (pintype "passive"))
    )
    (net (code "62") (name "Net-(R38-Pad1)") (class "Default")
      (node (ref "R38") (pin "1") (pinfunction "1_1") (pintype "passive"))
      (node (ref "SW2") (pin "1") (pinfunction "1_1") (pintype "passive"))
    )
    (net (code "63") (name "Net-(R40-Pad1)") (class "Default")
      (node (ref "R40") (pin "1") (pinfunction "1_1") (pintype "passive"))
      (node (ref "SW3") (pin "1") (pinfunction "1_1") (pintype "passive"))
    )
    (net (code "64") (name "Net-(U11-~{HOLD})") (class "Default")
      (node (ref "R31") (pin "2") (pinfunction "2_2") (pintype "passive"))
      (node (ref "U11") (pin "7") (pinfunction "~{HOLD}_7") (pintype "input"))
    )
    (net (code "65") (name "OС_0") (class "Default")
      (node (ref "U10") (pin "62") (pinfunction "PD15_62") (pintype "bidirectional"))
    )
    (net (code "66") (name "OС_1") (class "Default")
      (node (ref "U10") (pin "61") (pinfunction "PD14_61") (pintype "bidirectional"))
    )
    (net (code "67") (name "OС_2") (class "Default")
      (node (ref "U10") (pin "60") (pinfunction "PD13_60") (pintype "bidirectional"))
    )
    (net (code "68") (name "OС_3") (class "Default")
      (node (ref "U10") (pin "59") (pinfunction "PD12_59") (pintype "bidirectional"))
    )
    (net (code "69") (name "SUPPLY_INT") (class "Default")
      (node (ref "U10") (pin "46") (pinfunction "PE15_46") (pintype "bidirectional"))
    )
    (net (code "70") (name "UART_7_RX") (class "Default")
      (node (ref "U10") (pin "38") (pinfunction "PE7_38") (pintype "bidirectional"))
    )
    (net (code "71") (name "UART_7_TX") (class "Default")
      (node (ref "U10") (pin "39") (pinfunction "PE8_39") (pintype "bidirectional"))
    )
    (net (code "72") (name "unconnected-(SW1-Pad2)") (class "Default")
      (node (ref "SW1") (pin "2") (pinfunction "2_2") (pintype "passive"))
    )
    (net (code "73") (name "unconnected-(SW1-Pad4)") (class "Default")
      (node (ref "SW1") (pin "4") (pinfunction "4_4") (pintype "passive"))
    )
    (net (code "74") (name "unconnected-(SW2-Pad2)") (class "Default")
      (node (ref "SW2") (pin "2") (pinfunction "2_2") (pintype "passive"))
    )
    (net (code "75") (name "unconnected-(SW2-Pad4)") (class "Default")
      (node (ref "SW2") (pin "4") (pinfunction "4_4") (pintype "passive"))
    )
    (net (code "76") (name "unconnected-(SW3-Pad2)") (class "Default")
      (node (ref "SW3") (pin "2") (pinfunction "2_2") (pintype "passive"))
    )
    (net (code "77") (name "unconnected-(SW3-Pad4)") (class "Default")
      (node (ref "SW3") (pin "4") (pinfunction "4_4") (pintype "passive"))
    )
    (net (code "78") (name "unconnected-(U4-I{slash}O_4-Pad6)") (class "Default")
      (node (ref "U4") (pin "6") (pinfunction "I/O_4_6") (pintype "passive"))
    )
    (net (code "79") (name "unconnected-(U9-I{slash}O_2-Pad3)") (class "Default")
      (node (ref "U9") (pin "3") (pinfunction "I/O_2_3") (pintype "passive"))
    )
    (net (code "80") (name "unconnected-(U9-I{slash}O_3-Pad4)") (class "Default")
      (node (ref "U9") (pin "4") (pinfunction "I/O_3_4") (pintype "passive"))
    )
    (net (code "81") (name "unconnected-(U10A-PA9-Pad68)") (class "Default")
      (node (ref "U10") (pin "68") (pinfunction "PA9_68") (pintype "bidirectional"))
    )
    (net (code "82") (name "unconnected-(U10A-PA10-Pad69)") (class "Default")
      (node (ref "U10") (pin "69") (pinfunction "PA10_69") (pintype "bidirectional"))
    )
    (net (code "83") (name "unconnected-(U10A-PA11-Pad70)") (class "Default")
      (node (ref "U10") (pin "70") (pinfunction "PA11_70") (pintype "bidirectional"))
    )
    (net (code "84") (name "unconnected-(U10A-PB2-BOOT1(PB2)-Pad37)") (class "Default")
      (node (ref "U10") (pin "37") (pinfunction "PB2-BOOT1(PB2)_37") (pintype "bidirectional"))
    )
    (net (code "85") (name "unconnected-(U10A-PB3(JTDO{slash}TRACESWO)-Pad89)") (class "Default")
      (node (ref "U10") (pin "89") (pinfunction "PB3(JTDO/TRACESWO)_89") (pintype "bidirectional"))
    )
    (net (code "86") (name "unconnected-(U10A-PB6-Pad92)") (class "Default")
      (node (ref "U10") (pin "92") (pinfunction "PB6_92") (pintype "bidirectional"))
    )
    (net (code "87") (name "unconnected-(U10A-PB12-Pad51)") (class "Default")
      (node (ref "U10") (pin "51") (pinfunction "PB12_51") (pintype "bidirectional"))
    )
    (net (code "88") (name "unconnected-(U10A-PB13-Pad52)") (class "Default")
      (node (ref "U10") (pin "52") (pinfunction "PB13_52") (pintype "bidirectional"))
    )
    (net (code "89") (name "unconnected-(U10A-PB14-Pad53)") (class "Default")
      (node (ref "U10") (pin "53") (pinfunction "PB14_53") (pintype "bidirectional"))
    )
    (net (code "90") (name "unconnected-(U10A-PB15-Pad54)") (class "Default")
      (node (ref "U10") (pin "54") (pinfunction "PB15_54") (pintype "bidirectional"))
    )
    (net (code "91") (name "unconnected-(U10A-PC0-Pad15)") (class "Default")
      (node (ref "U10") (pin "15") (pinfunction "PC0_15") (pintype "bidirectional"))
    )
    (net (code "92") (name "unconnected-(U10A-PC1-Pad16)") (class "Default")
      (node (ref "U10") (pin "16") (pinfunction "PC1_16") (pintype "bidirectional"))
    )
    (net (code "93") (name "unconnected-(U10A-PC2-Pad17)") (class "Default")
      (node (ref "U10") (pin "17") (pinfunction "PC2_17") (pintype "bidirectional"))
    )
    (net (code "94") (name "unconnected-(U10A-PC3-Pad18)") (class "Default")
      (node (ref "U10") (pin "18") (pinfunction "PC3_18") (pintype "bidirectional"))
    )
    (net (code "95") (name "unconnected-(U10A-PC5-Pad34)") (class "Default")
      (node (ref "U10") (pin "34") (pinfunction "PC5_34") (pintype "bidirectional"))
    )
    (net (code "96") (name "unconnected-(U10A-PC6-Pad63)") (class "Default")
      (node (ref "U10") (pin "63") (pinfunction "PC6_63") (pintype "bidirectional"))
    )
    (net (code "97") (name "unconnected-(U10A-PC7-Pad64)") (class "Default")
      (node (ref "U10") (pin "64") (pinfunction "PC7_64") (pintype "bidirectional"))
    )
    (net (code "98") (name "unconnected-(U10A-PC8-Pad65)") (class "Default")
      (node (ref "U10") (pin "65") (pinfunction "PC8_65") (pintype "bidirectional"))
    )
    (net (code "99") (name "unconnected-(U10A-PC13-Pad7)") (class "Default")
      (node (ref "U10") (pin "7") (pinfunction "PC13_7") (pintype "bidirectional"))
    )
    (net (code "100") (name "unconnected-(U10A-PC14-OSC32_IN(PC14)-Pad8)") (class "Default")
      (node (ref "U10") (pin "8") (pinfunction "PC14-OSC32_IN(PC14)_8") (pintype "bidirectional"))
    )
    (net (code "101") (name "unconnected-(U10A-PC15-OSC32_OUT(PC15)-Pad9)") (class "Default")
      (node (ref "U10") (pin "9") (pinfunction "PC15-OSC32_OUT(PC15)_9") (pintype "bidirectional"))
    )
    (net (code "102") (name "unconnected-(U10A-PD1-Pad82)") (class "Default")
      (node (ref "U10") (pin "82") (pinfunction "PD1_82") (pintype "bidirectional"))
    )
    (net (code "103") (name "unconnected-(U10A-PD2-Pad83)") (class "Default")
      (node (ref "U10") (pin "83") (pinfunction "PD2_83") (pintype "bidirectional"))
    )
    (net (code "104") (name "unconnected-(U10A-PD3-Pad84)") (class "Default")
      (node (ref "U10") (pin "84") (pinfunction "PD3_84") (pintype "bidirectional"))
    )
    (net (code "105") (name "unconnected-(U10A-PD4-Pad85)") (class "Default")
      (node (ref "U10") (pin "85") (pinfunction "PD4_85") (pintype "bidirectional"))
    )
    (net (code "106") (name "unconnected-(U10A-PD5-Pad86)") (class "Default")
      (node (ref "U10") (pin "86") (pinfunction "PD5_86") (pintype "bidirectional"))
    )
    (net (code "107") (name "unconnected-(U10A-PD6-Pad87)") (class "Default")
      (node (ref "U10") (pin "87") (pinfunction "PD6_87") (pintype "bidirectional"))
    )
    (net (code "108") (name "unconnected-(U10A-PD7-Pad88)") (class "Default")
      (node (ref "U10") (pin "88") (pinfunction "PD7_88") (pintype "bidirectional"))
    )
    (net (code "109") (name "unconnected-(U10A-PD11-Pad58)") (class "Default")
      (node (ref "U10") (pin "58") (pinfunction "PD11_58") (pintype "bidirectional"))
    )
    (net (code "110") (name "unconnected-(U10A-PE0-Pad97)") (class "Default")
      (node (ref "U10") (pin "97") (pinfunction "PE0_97") (pintype "bidirectional"))
    )
    (net (code "111") (name "unconnected-(U10A-PE1-Pad98)") (class "Default")
      (node (ref "U10") (pin "98") (pinfunction "PE1_98") (pintype "bidirectional"))
    )
    (net (code "112") (name "unconnected-(U10A-PE2-Pad1)") (class "Default")
      (node (ref "U10") (pin "1") (pinfunction "PE2_1") (pintype "bidirectional"))
    )
    (net (code "113") (name "unconnected-(U10A-PE6-Pad5)") (class "Default")
      (node (ref "U10") (pin "5") (pinfunction "PE6_5") (pintype "bidirectional"))
    )
    (net (code "114") (name "unconnected-(U10A-PE9-Pad40)") (class "Default")
      (node (ref "U10") (pin "40") (pinfunction "PE9_40") (pintype "bidirectional"))
    )
    (net (code "115") (name "unconnected-(U10A-PE10-Pad41)") (class "Default")
      (node (ref "U10") (pin "41") (pinfunction "PE10_41") (pintype "bidirectional"))
    )
    (net (code "116") (name "unconnected-(U10A-PE11-Pad42)") (class "Default")
      (node (ref "U10") (pin "42") (pinfunction "PE11_42") (pintype "bidirectional"))
    )
    (net (code "117") (name "unconnected-(U10A-PE12-Pad43)") (class "Default")
      (node (ref "U10") (pin "43") (pinfunction "PE12_43") (pintype "bidirectional"))
    )
    (net (code "118") (name "unconnected-(U10A-PE13-Pad44)") (class "Default")
      (node (ref "U10") (pin "44") (pinfunction "PE13_44") (pintype "bidirectional"))
    )
    (net (code "119") (name "unconnected-(U10A-PE14-Pad45)") (class "Default")
      (node (ref "U10") (pin "45") (pinfunction "PE14_45") (pintype "bidirectional"))
    )
    (net (code "120") (name "unconnected-(VD4-A-Pad1)") (class "Default")
      (node (ref "VD4") (pin "1") (pinfunction "A_1") (pintype "passive"))
    )
  )
)
